# base.net
KiCad netlist of a schematic drawn in Altium Designer
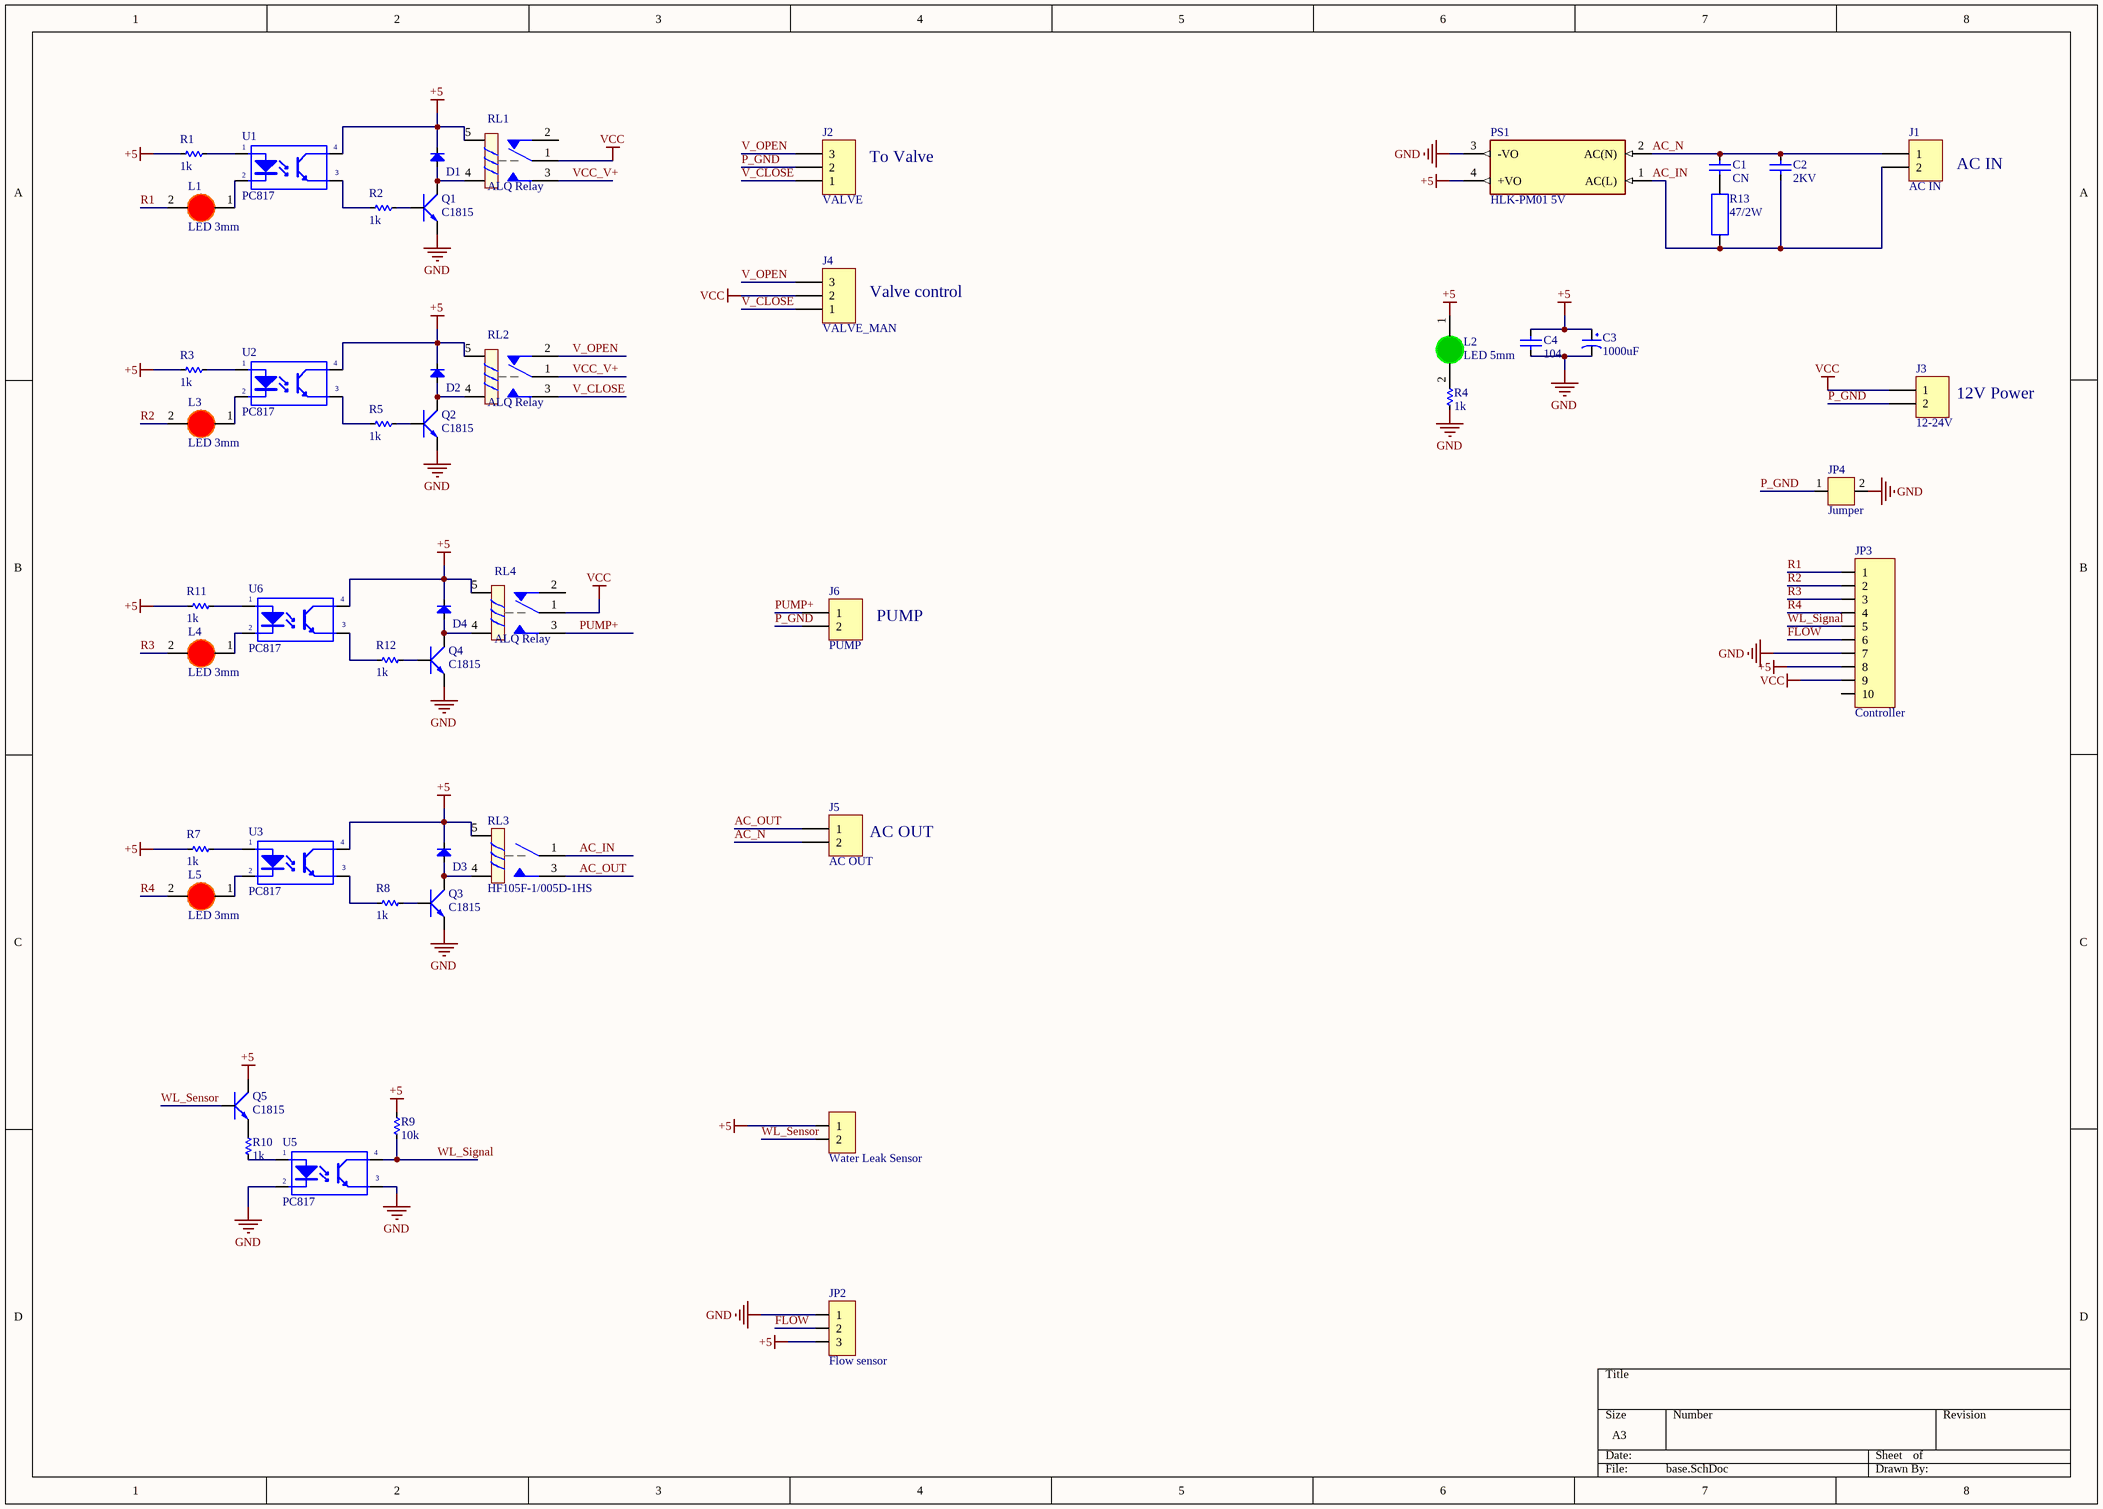
[diagram p0: base.SchDoc]

(export (version "E")
  (design (tool "Eeschema 10.0.6"))
  (components
    (comp (ref "C1")
      (value "CN")
      (footprint "Cap 15mm")
      (description "Capacitor")
      (libsource (lib "iuh-thuc-hanh") (part "CN"))
    )
    (comp (ref "C2")
      (value "2KV")
      (footprint "Cap 7.5mm")
      (description "Capacitor Ceramic 2KV")
      (libsource (lib "iuh-thuc-hanh") (part "Cap 103 2KV"))
    )
    (comp (ref "C3")
      (value "1000uF")
      (footprint "tu hoa 8mm")
      (description "Cắm")
      (libsource (lib "Altium_Lib_by_KhueNguyenCreator") (part "Tu Hoa 1000uF 16V 8x20"))
    )
    (comp (ref "C4")
      (value "104")
      (footprint "Cap 2.54mm")
      (description "Capacitor")
      (libsource (lib "iuh-thuc-hanh") (part "CN"))
    )
    (comp (ref "D1")
      (value "Diode")
      (footprint "DIO-1A")
      (description "Default Diode")
      (fields (field (name "PUBLISHER") "Altium Limited"))
      (libsource (lib "LIBRARY1") (part "Diode"))
    )
    (comp (ref "D2")
      (value "Diode")
      (footprint "DIO-1A")
      (description "Default Diode")
      (fields (field (name "PUBLISHER") "Altium Limited"))
      (libsource (lib "LIBRARY1") (part "Diode"))
    )
    (comp (ref "D3")
      (value "Diode")
      (footprint "DIO-1A")
      (description "Default Diode")
      (fields (field (name "PUBLISHER") "Altium Limited"))
      (libsource (lib "LIBRARY1") (part "Diode"))
    )
    (comp (ref "D4")
      (value "Diode")
      (footprint "DIO-1A")
      (description "Default Diode")
      (fields (field (name "PUBLISHER") "Altium Limited"))
      (libsource (lib "LIBRARY1") (part "Diode"))
    )
    (comp (ref "J1")
      (value "AC IN")
      (footprint "CON 2 2EDG5.08")
      (description "CON2 KF terminal")
      (libsource (lib "iuh-thuc-hanh") (part "CON 2 EDG5.08"))
    )
    (comp (ref "J2")
      (value "VALVE")
      (footprint "CON 3 2EDG5.08")
      (description "CON3 KF terminal")
      (libsource (lib "iuh-thuc-hanh") (part "CON 3 EDG5.08"))
    )
    (comp (ref "J3")
      (value "12-24V")
      (footprint "CON 2 2EDG5.08")
      (description "CON2 KF terminal")
      (libsource (lib "iuh-thuc-hanh") (part "CON 2 EDG5.08"))
    )
    (comp (ref "J4")
      (value "VALVE_MAN")
      (footprint "CON 3 2EDG5.08")
      (description "CON3 KF terminal")
      (libsource (lib "iuh-thuc-hanh") (part "CON 3 EDG5.08"))
    )
    (comp (ref "J5")
      (value "AC OUT")
      (footprint "CON 2 2EDG5.08")
      (description "CON2 KF terminal")
      (libsource (lib "iuh-thuc-hanh") (part "CON 2 EDG5.08"))
    )
    (comp (ref "J6")
      (value "PUMP")
      (footprint "CON 2 2EDG5.08")
      (description "CON2 KF terminal")
      (libsource (lib "iuh-thuc-hanh") (part "CON 2 EDG5.08"))
    )
    (comp (ref "JP1")
      (value "Water Leak Sensor")
      (footprint "JP 1x2 CT")
      (description "Cắm")
      (libsource (lib "Altium_Lib_by_KhueNguyenCreator") (part "JP 1x2 2.54 Cai Thang"))
    )
    (comp (ref "JP2")
      (value "Flow sensor")
      (footprint "JP 1x3 DT")
      (description "Cắm")
      (libsource (lib "Altium_Lib_by_KhueNguyenCreator") (part "JP 1x3 2.54 Duc Thang"))
    )
    (comp (ref "JP3")
      (value "Controller")
      (footprint "JP 1x10 CT")
      (description "Cắm")
      (libsource (lib "Altium_Lib_by_KhueNguyenCreator") (part "JP 1x10 2.54 Cai Thang"))
    )
    (comp (ref "JP4")
      (value "Jumper")
      (footprint "Jumper 5.08")
      (description "jump 2.54 jump 5.08")
      (libsource (lib "iuh-thuc-hanh") (part "Jumper"))
    )
    (comp (ref "L1")
      (value "LED 3mm")
      (footprint "LED-3MM-RED")
      (description "Cắm")
      (libsource (lib "Altium_Lib_by_KhueNguyenCreator") (part "LED 3mm Do"))
    )
    (comp (ref "L2")
      (value "LED 5mm")
      (footprint "LED-5MM-Green")
      (description "Cắm")
      (libsource (lib "Altium_Lib_by_KhueNguyenCreator") (part "LED 5mm Xanh La"))
    )
    (comp (ref "L3")
      (value "LED 3mm")
      (footprint "LED-3MM-RED")
      (description "Cắm")
      (libsource (lib "Altium_Lib_by_KhueNguyenCreator") (part "LED 3mm Do"))
    )
    (comp (ref "L4")
      (value "LED 3mm")
      (footprint "LED-3MM-RED")
      (description "Cắm")
      (libsource (lib "Altium_Lib_by_KhueNguyenCreator") (part "LED 3mm Do"))
    )
    (comp (ref "L5")
      (value "LED 3mm")
      (footprint "LED-3MM-RED")
      (description "Cắm")
      (libsource (lib "Altium_Lib_by_KhueNguyenCreator") (part "LED 3mm Do"))
    )
    (comp (ref "PS1")
      (value "HLK-PM01 5V")
      (footprint "CONV_HLK-PM01")
      (description "220VAC to 5V 3W")
      (fields (field (name "MF") "Hi-link") (field (name "MP") "HLK-20M12"))
      (libsource (lib "iuh-thuc-hanh") (part "CONV HLK-PM01"))
    )
    (comp (ref "Q1")
      (value "C1815")
      (footprint "TO92")
      (description "NPN transistor")
      (libsource (lib "Altium_Lib_by_KhueNguyenCreator") (part "Trans C1815 DIP"))
    )
    (comp (ref "Q2")
      (value "C1815")
      (footprint "TO92")
      (description "NPN transistor")
      (libsource (lib "Altium_Lib_by_KhueNguyenCreator") (part "Trans C1815 DIP"))
    )
    (comp (ref "Q3")
      (value "C1815")
      (footprint "TO92")
      (description "NPN transistor")
      (libsource (lib "Altium_Lib_by_KhueNguyenCreator") (part "Trans C1815 DIP"))
    )
    (comp (ref "Q4")
      (value "C1815")
      (footprint "TO92")
      (description "NPN transistor")
      (libsource (lib "Altium_Lib_by_KhueNguyenCreator") (part "Trans C1815 DIP"))
    )
    (comp (ref "Q5")
      (value "C1815")
      (footprint "TO92")
      (description "NPN transistor")
      (libsource (lib "Altium_Lib_by_KhueNguyenCreator") (part "Trans C1815 DIP"))
    )
    (comp (ref "R1")
      (value "1k")
      (footprint "RES-1/4W")
      (description "Res")
      (fields
        (field (name "MANUFACTURER") "Generic Components")
        (field (name "PUBLISHER") "Altium Hobart Technology Centre")
      )
      (libsource (lib "LIBRARY1") (part "Res"))
    )
    (comp (ref "R2")
      (value "1k")
      (footprint "RES-1/4W")
      (description "Res")
      (fields
        (field (name "MANUFACTURER") "Generic Components")
        (field (name "PUBLISHER") "Altium Hobart Technology Centre")
      )
      (libsource (lib "LIBRARY1") (part "Res"))
    )
    (comp (ref "R3")
      (value "1k")
      (footprint "RES-1/4W")
      (description "Res")
      (fields
        (field (name "MANUFACTURER") "Generic Components")
        (field (name "PUBLISHER") "Altium Hobart Technology Centre")
      )
      (libsource (lib "LIBRARY1") (part "Res"))
    )
    (comp (ref "R4")
      (value "1k")
      (footprint "RES-1/4W")
      (description "Res")
      (fields
        (field (name "MANUFACTURER") "Generic Components")
        (field (name "PUBLISHER") "Altium Hobart Technology Centre")
      )
      (libsource (lib "LIBRARY1") (part "Res"))
    )
    (comp (ref "R5")
      (value "1k")
      (footprint "RES-1/4W")
      (description "Res")
      (fields
        (field (name "MANUFACTURER") "Generic Components")
        (field (name "PUBLISHER") "Altium Hobart Technology Centre")
      )
      (libsource (lib "LIBRARY1") (part "Res"))
    )
    (comp (ref "R7")
      (value "1k")
      (footprint "RES-1/4W")
      (description "Res")
      (fields
        (field (name "MANUFACTURER") "Generic Components")
        (field (name "PUBLISHER") "Altium Hobart Technology Centre")
      )
      (libsource (lib "LIBRARY1") (part "Res"))
    )
    (comp (ref "R8")
      (value "1k")
      (footprint "RES-1/4W")
      (description "Res")
      (fields
        (field (name "MANUFACTURER") "Generic Components")
        (field (name "PUBLISHER") "Altium Hobart Technology Centre")
      )
      (libsource (lib "LIBRARY1") (part "Res"))
    )
    (comp (ref "R9")
      (value "10k")
      (footprint "RES-1/4WD")
      (description "Res")
      (fields
        (field (name "MANUFACTURER") "Generic Components")
        (field (name "PUBLISHER") "Altium Hobart Technology Centre")
      )
      (libsource (lib "LIBRARY1") (part "Res"))
    )
    (comp (ref "R10")
      (value "1k")
      (footprint "RES-1/4WD")
      (description "Res")
      (fields
        (field (name "MANUFACTURER") "Generic Components")
        (field (name "PUBLISHER") "Altium Hobart Technology Centre")
      )
      (libsource (lib "LIBRARY1") (part "Res"))
    )
    (comp (ref "R11")
      (value "1k")
      (footprint "RES-1/4W")
      (description "Res")
      (fields
        (field (name "MANUFACTURER") "Generic Components")
        (field (name "PUBLISHER") "Altium Hobart Technology Centre")
      )
      (libsource (lib "LIBRARY1") (part "Res"))
    )
    (comp (ref "R12")
      (value "1k")
      (footprint "RES-1/4W")
      (description "Res")
      (fields
        (field (name "MANUFACTURER") "Generic Components")
        (field (name "PUBLISHER") "Altium Hobart Technology Centre")
      )
      (libsource (lib "LIBRARY1") (part "Res"))
    )
    (comp (ref "R13")
      (value "47/2W")
      (footprint "R2WD")
      (description "Resistor 2W")
      (libsource (lib "iuh-thuc-hanh") (part "R2W"))
    )
    (comp (ref "RL1")
      (value "ALQ Relay")
      (footprint "Relay-LQ-form-C")
      (description "ALQ Relay 10A")
      (libsource (lib "iuh-thuc-hanh") (part "Relay Panasonic LQ"))
    )
    (comp (ref "RL2")
      (value "ALQ Relay")
      (footprint "Relay-LQ-form-C")
      (description "ALQ Relay 10A")
      (libsource (lib "iuh-thuc-hanh") (part "Relay Panasonic LQ"))
    )
    (comp (ref "RL3")
      (value "HF105F-1/005D-1HS")
      (footprint "Relay-HF-30A-Form-A")
      (description "Relay hongfa 30A 4P HF105F-1/005D-1HS")
      (libsource (lib "iuh-thuc-hanh") (part "Relay 30A 4P"))
    )
    (comp (ref "RL4")
      (value "ALQ Relay")
      (footprint "Relay-LQ-form-C")
      (description "ALQ Relay 10A")
      (libsource (lib "iuh-thuc-hanh") (part "Relay Panasonic LQ"))
    )
    (comp (ref "U1")
      (value "PC817")
      (footprint "DIP4")
      (description "Single Opto")
      (libsource (lib "LIBRARY1") (part "PC817"))
    )
    (comp (ref "U2")
      (value "PC817")
      (footprint "DIP4")
      (description "Single Opto")
      (libsource (lib "LIBRARY1") (part "PC817"))
    )
    (comp (ref "U3")
      (value "PC817")
      (footprint "DIP4")
      (description "Single Opto")
      (libsource (lib "LIBRARY1") (part "PC817"))
    )
    (comp (ref "U5")
      (value "PC817")
      (footprint "DIP4")
      (description "Single Opto")
      (libsource (lib "LIBRARY1") (part "PC817"))
    )
    (comp (ref "U6")
      (value "PC817")
      (footprint "DIP4")
      (description "Single Opto")
      (libsource (lib "LIBRARY1") (part "PC817"))
    )
  )
  (nets
    (net (code "1") (name "+5") (class "Default")
      (node (ref "C3") (pin "1") (pinfunction "1_1") (pintype "passive"))
      (node (ref "C4") (pin "2") (pinfunction "2_2") (pintype "passive"))
      (node (ref "D1") (pin "2") (pinfunction "K_2") (pintype "passive"))
      (node (ref "D2") (pin "2") (pinfunction "K_2") (pintype "passive"))
      (node (ref "D3") (pin "2") (pinfunction "K_2") (pintype "passive"))
      (node (ref "D4") (pin "2") (pinfunction "K_2") (pintype "passive"))
      (node (ref "JP1") (pin "1") (pinfunction "1_1") (pintype "passive"))
      (node (ref "JP2") (pin "3") (pinfunction "3_3") (pintype "passive"))
      (node (ref "JP3") (pin "8") (pinfunction "8_8") (pintype "passive"))
      (node (ref "L2") (pin "1") (pinfunction "A_1") (pintype "passive"))
      (node (ref "PS1") (pin "4") (pinfunction "+VO_4") (pintype "output"))
      (node (ref "Q5") (pin "2") (pinfunction "C_2") (pintype "passive"))
      (node (ref "R1") (pin "1") (pinfunction "1_1") (pintype "passive"))
      (node (ref "R11") (pin "1") (pinfunction "1_1") (pintype "passive"))
      (node (ref "R3") (pin "1") (pinfunction "1_1") (pintype "passive"))
      (node (ref "R7") (pin "1") (pinfunction "1_1") (pintype "passive"))
      (node (ref "R9") (pin "2") (pinfunction "2_2") (pintype "passive"))
      (node (ref "RL1") (pin "5") (pinfunction "5_5") (pintype "passive"))
      (node (ref "RL2") (pin "5") (pinfunction "5_5") (pintype "passive"))
      (node (ref "RL3") (pin "5") (pinfunction "5_5") (pintype "passive"))
      (node (ref "RL4") (pin "5") (pinfunction "5_5") (pintype "passive"))
      (node (ref "U1") (pin "4") (pinfunction "C_4") (pintype "passive"))
      (node (ref "U2") (pin "4") (pinfunction "C_4") (pintype "passive"))
      (node (ref "U3") (pin "4") (pinfunction "C_4") (pintype "passive"))
      (node (ref "U6") (pin "4") (pinfunction "C_4") (pintype "passive"))
    )
    (net (code "2") (name "/AC_IN") (class "Default")
      (node (ref "C2") (pin "2") (pinfunction "2_2") (pintype "passive"))
      (node (ref "J1") (pin "2") (pinfunction "2_2") (pintype "passive"))
      (node (ref "PS1") (pin "1") (pinfunction "AC(L)_1") (pintype "input"))
      (node (ref "R13") (pin "2") (pinfunction "2_2") (pintype "passive"))
      (node (ref "RL3") (pin "1") (pinfunction "1_1") (pintype "passive"))
    )
    (net (code "3") (name "/AC_N") (class "Default")
      (node (ref "C1") (pin "2") (pinfunction "2_2") (pintype "passive"))
      (node (ref "C2") (pin "1") (pinfunction "1_1") (pintype "passive"))
      (node (ref "J1") (pin "1") (pinfunction "1_1") (pintype "passive"))
      (node (ref "J5") (pin "2") (pinfunction "2_2") (pintype "passive"))
      (node (ref "PS1") (pin "2") (pinfunction "AC(N)_2") (pintype "input"))
    )
    (net (code "4") (name "/AC_OUT") (class "Default")
      (node (ref "J5") (pin "1") (pinfunction "1_1") (pintype "passive"))
      (node (ref "RL3") (pin "3") (pinfunction "3_3") (pintype "passive"))
    )
    (net (code "5") (name "/FLOW") (class "Default")
      (node (ref "JP2") (pin "2") (pinfunction "2_2") (pintype "passive"))
      (node (ref "JP3") (pin "6") (pinfunction "6_6") (pintype "passive"))
    )
    (net (code "6") (name "/PUMP+") (class "Default")
      (node (ref "J6") (pin "1") (pinfunction "1_1") (pintype "passive"))
      (node (ref "RL4") (pin "3") (pinfunction "3_3") (pintype "passive"))
    )
    (net (code "7") (name "/P_GND") (class "Default")
      (node (ref "J2") (pin "2") (pinfunction "2_2") (pintype "passive"))
      (node (ref "J3") (pin "2") (pinfunction "2_2") (pintype "passive"))
      (node (ref "J6") (pin "2") (pinfunction "2_2") (pintype "passive"))
      (node (ref "JP4") (pin "1") (pintype "passive"))
    )
    (net (code "8") (name "/R1") (class "Default")
      (node (ref "JP3") (pin "1") (pinfunction "1_1") (pintype "passive"))
      (node (ref "L1") (pin "2") (pinfunction "K_2") (pintype "passive"))
    )
    (net (code "9") (name "/R2") (class "Default")
      (node (ref "JP3") (pin "2") (pinfunction "2_2") (pintype "passive"))
      (node (ref "L3") (pin "2") (pinfunction "K_2") (pintype "passive"))
    )
    (net (code "10") (name "/R3") (class "Default")
      (node (ref "JP3") (pin "3") (pinfunction "3_3") (pintype "passive"))
      (node (ref "L4") (pin "2") (pinfunction "K_2") (pintype "passive"))
    )
    (net (code "11") (name "/R4") (class "Default")
      (node (ref "JP3") (pin "4") (pinfunction "4_4") (pintype "passive"))
      (node (ref "L5") (pin "2") (pinfunction "K_2") (pintype "passive"))
    )
    (net (code "12") (name "/VCC_V+") (class "Default")
      (node (ref "RL1") (pin "3") (pinfunction "3_3") (pintype "passive"))
      (node (ref "RL2") (pin "1") (pinfunction "1_1") (pintype "passive"))
    )
    (net (code "13") (name "/V_CLOSE") (class "Default")
      (node (ref "J2") (pin "1") (pinfunction "1_1") (pintype "passive"))
      (node (ref "J4") (pin "1") (pinfunction "1_1") (pintype "passive"))
      (node (ref "RL2") (pin "3") (pinfunction "3_3") (pintype "passive"))
    )
    (net (code "14") (name "/V_OPEN") (class "Default")
      (node (ref "J2") (pin "3") (pinfunction "3_3") (pintype "passive"))
      (node (ref "J4") (pin "3") (pinfunction "3_3") (pintype "passive"))
      (node (ref "RL2") (pin "2") (pinfunction "2_2") (pintype "passive"))
    )
    (net (code "15") (name "/WL_Sensor") (class "Default")
      (node (ref "JP1") (pin "2") (pinfunction "2_2") (pintype "passive"))
      (node (ref "Q5") (pin "3") (pinfunction "B_3") (pintype "passive"))
    )
    (net (code "16") (name "/WL_Signal") (class "Default")
      (node (ref "JP3") (pin "5") (pinfunction "5_5") (pintype "passive"))
      (node (ref "R9") (pin "1") (pinfunction "1_1") (pintype "passive"))
      (node (ref "U5") (pin "4") (pinfunction "C_4") (pintype "passive"))
    )
    (net (code "17") (name "GND") (class "Default")
      (node (ref "C3") (pin "2") (pinfunction "2_2") (pintype "passive"))
      (node (ref "C4") (pin "1") (pinfunction "1_1") (pintype "passive"))
      (node (ref "JP2") (pin "1") (pinfunction "1_1") (pintype "passive"))
      (node (ref "JP3") (pin "7") (pinfunction "7_7") (pintype "passive"))
      (node (ref "JP4") (pin "2") (pintype "passive"))
      (node (ref "PS1") (pin "3") (pinfunction "-VO_3") (pintype "output"))
      (node (ref "Q1") (pin "1") (pinfunction "E_1") (pintype "passive"))
      (node (ref "Q2") (pin "1") (pinfunction "E_1") (pintype "passive"))
      (node (ref "Q3") (pin "1") (pinfunction "E_1") (pintype "passive"))
      (node (ref "Q4") (pin "1") (pinfunction "E_1") (pintype "passive"))
      (node (ref "R4") (pin "1") (pinfunction "1_1") (pintype "passive"))
      (node (ref "U5") (pin "2") (pinfunction "K_2") (pintype "passive"))
      (node (ref "U5") (pin "3") (pinfunction "E_3") (pintype "passive"))
    )
    (net (code "18") (name "Net-(C1-Pad1)") (class "Default")
      (node (ref "C1") (pin "1") (pinfunction "1_1") (pintype "passive"))
      (node (ref "R13") (pin "1") (pinfunction "1_1") (pintype "passive"))
    )
    (net (code "19") (name "Net-(D1-A)") (class "Default")
      (node (ref "D1") (pin "1") (pinfunction "A_1") (pintype "passive"))
      (node (ref "Q1") (pin "2") (pinfunction "C_2") (pintype "passive"))
      (node (ref "RL1") (pin "4") (pinfunction "4_4") (pintype "passive"))
    )
    (net (code "20") (name "Net-(D2-A)") (class "Default")
      (node (ref "D2") (pin "1") (pinfunction "A_1") (pintype "passive"))
      (node (ref "Q2") (pin "2") (pinfunction "C_2") (pintype "passive"))
      (node (ref "RL2") (pin "4") (pinfunction "4_4") (pintype "passive"))
    )
    (net (code "21") (name "Net-(D3-A)") (class "Default")
      (node (ref "D3") (pin "1") (pinfunction "A_1") (pintype "passive"))
      (node (ref "Q3") (pin "2") (pinfunction "C_2") (pintype "passive"))
      (node (ref "RL3") (pin "4") (pinfunction "4_4") (pintype "passive"))
    )
    (net (code "22") (name "Net-(D4-A)") (class "Default")
      (node (ref "D4") (pin "1") (pinfunction "A_1") (pintype "passive"))
      (node (ref "Q4") (pin "2") (pinfunction "C_2") (pintype "passive"))
      (node (ref "RL4") (pin "4") (pinfunction "4_4") (pintype "passive"))
    )
    (net (code "23") (name "Net-(L1-A)") (class "Default")
      (node (ref "L1") (pin "1") (pinfunction "A_1") (pintype "passive"))
      (node (ref "U1") (pin "2") (pinfunction "K_2") (pintype "passive"))
    )
    (net (code "24") (name "Net-(L2-K)") (class "Default")
      (node (ref "L2") (pin "2") (pinfunction "K_2") (pintype "passive"))
      (node (ref "R4") (pin "2") (pinfunction "2_2") (pintype "passive"))
    )
    (net (code "25") (name "Net-(L3-A)") (class "Default")
      (node (ref "L3") (pin "1") (pinfunction "A_1") (pintype "passive"))
      (node (ref "U2") (pin "2") (pinfunction "K_2") (pintype "passive"))
    )
    (net (code "26") (name "Net-(L4-A)") (class "Default")
      (node (ref "L4") (pin "1") (pinfunction "A_1") (pintype "passive"))
      (node (ref "U6") (pin "2") (pinfunction "K_2") (pintype "passive"))
    )
    (net (code "27") (name "Net-(L5-A)") (class "Default")
      (node (ref "L5") (pin "1") (pinfunction "A_1") (pintype "passive"))
      (node (ref "U3") (pin "2") (pinfunction "K_2") (pintype "passive"))
    )
    (net (code "28") (name "Net-(Q1-B)") (class "Default")
      (node (ref "Q1") (pin "3") (pinfunction "B_3") (pintype "passive"))
      (node (ref "R2") (pin "2") (pinfunction "2_2") (pintype "passive"))
    )
    (net (code "29") (name "Net-(Q2-B)") (class "Default")
      (node (ref "Q2") (pin "3") (pinfunction "B_3") (pintype "passive"))
      (node (ref "R5") (pin "2") (pinfunction "2_2") (pintype "passive"))
    )
    (net (code "30") (name "Net-(Q3-B)") (class "Default")
      (node (ref "Q3") (pin "3") (pinfunction "B_3") (pintype "passive"))
      (node (ref "R8") (pin "2") (pinfunction "2_2") (pintype "passive"))
    )
    (net (code "31") (name "Net-(Q4-B)") (class "Default")
      (node (ref "Q4") (pin "3") (pinfunction "B_3") (pintype "passive"))
      (node (ref "R12") (pin "2") (pinfunction "2_2") (pintype "passive"))
    )
    (net (code "32") (name "Net-(Q5-E)") (class "Default")
      (node (ref "Q5") (pin "1") (pinfunction "E_1") (pintype "passive"))
      (node (ref "R10") (pin "2") (pinfunction "2_2") (pintype "passive"))
    )
    (net (code "33") (name "Net-(U1-A)") (class "Default")
      (node (ref "R1") (pin "2") (pinfunction "2_2") (pintype "passive"))
      (node (ref "U1") (pin "1") (pinfunction "A_1") (pintype "passive"))
    )
    (net (code "34") (name "Net-(U1-E)") (class "Default")
      (node (ref "R2") (pin "1") (pinfunction "1_1") (pintype "passive"))
      (node (ref "U1") (pin "3") (pinfunction "E_3") (pintype "passive"))
    )
    (net (code "35") (name "Net-(U2-A)") (class "Default")
      (node (ref "R3") (pin "2") (pinfunction "2_2") (pintype "passive"))
      (node (ref "U2") (pin "1") (pinfunction "A_1") (pintype "passive"))
    )
    (net (code "36") (name "Net-(U2-E)") (class "Default")
      (node (ref "R5") (pin "1") (pinfunction "1_1") (pintype "passive"))
      (node (ref "U2") (pin "3") (pinfunction "E_3") (pintype "passive"))
    )
    (net (code "37") (name "Net-(U3-A)") (class "Default")
      (node (ref "R7") (pin "2") (pinfunction "2_2") (pintype "passive"))
      (node (ref "U3") (pin "1") (pinfunction "A_1") (pintype "passive"))
    )
    (net (code "38") (name "Net-(U3-E)") (class "Default")
      (node (ref "R8") (pin "1") (pinfunction "1_1") (pintype "passive"))
      (node (ref "U3") (pin "3") (pinfunction "E_3") (pintype "passive"))
    )
    (net (code "39") (name "Net-(U5-A)") (class "Default")
      (node (ref "R10") (pin "1") (pinfunction "1_1") (pintype "passive"))
      (node (ref "U5") (pin "1") (pinfunction "A_1") (pintype "passive"))
    )
    (net (code "40") (name "Net-(U6-A)") (class "Default")
      (node (ref "R11") (pin "2") (pinfunction "2_2") (pintype "passive"))
      (node (ref "U6") (pin "1") (pinfunction "A_1") (pintype "passive"))
    )
    (net (code "41") (name "Net-(U6-E)") (class "Default")
      (node (ref "R12") (pin "1") (pinfunction "1_1") (pintype "passive"))
      (node (ref "U6") (pin "3") (pinfunction "E_3") (pintype "passive"))
    )
    (net (code "42") (name "VCC") (class "Default")
      (node (ref "J3") (pin "1") (pinfunction "1_1") (pintype "passive"))
      (node (ref "J4") (pin "2") (pinfunction "2_2") (pintype "passive"))
      (node (ref "JP3") (pin "9") (pinfunction "9_9") (pintype "passive"))
      (node (ref "RL1") (pin "1") (pinfunction "1_1") (pintype "passive"))
      (node (ref "RL4") (pin "1") (pinfunction "1_1") (pintype "passive"))
    )
    (net (code "43") (name "unconnected-(JP3-Pad10)") (class "Default")
      (node (ref "JP3") (pin "10") (pinfunction "10_10") (pintype "passive"))
    )
    (net (code "44") (name "unconnected-(RL1-Pad2)") (class "Default")
      (node (ref "RL1") (pin "2") (pinfunction "2_2") (pintype "passive"))
    )
    (net (code "45") (name "unconnected-(RL4-Pad2)") (class "Default")
      (node (ref "RL4") (pin "2") (pinfunction "2_2") (pintype "passive"))
    )
  )
)
